# LoRaWAN_CC1310_V1_1.net
KiCad netlist of a schematic drawn in Altium Designer
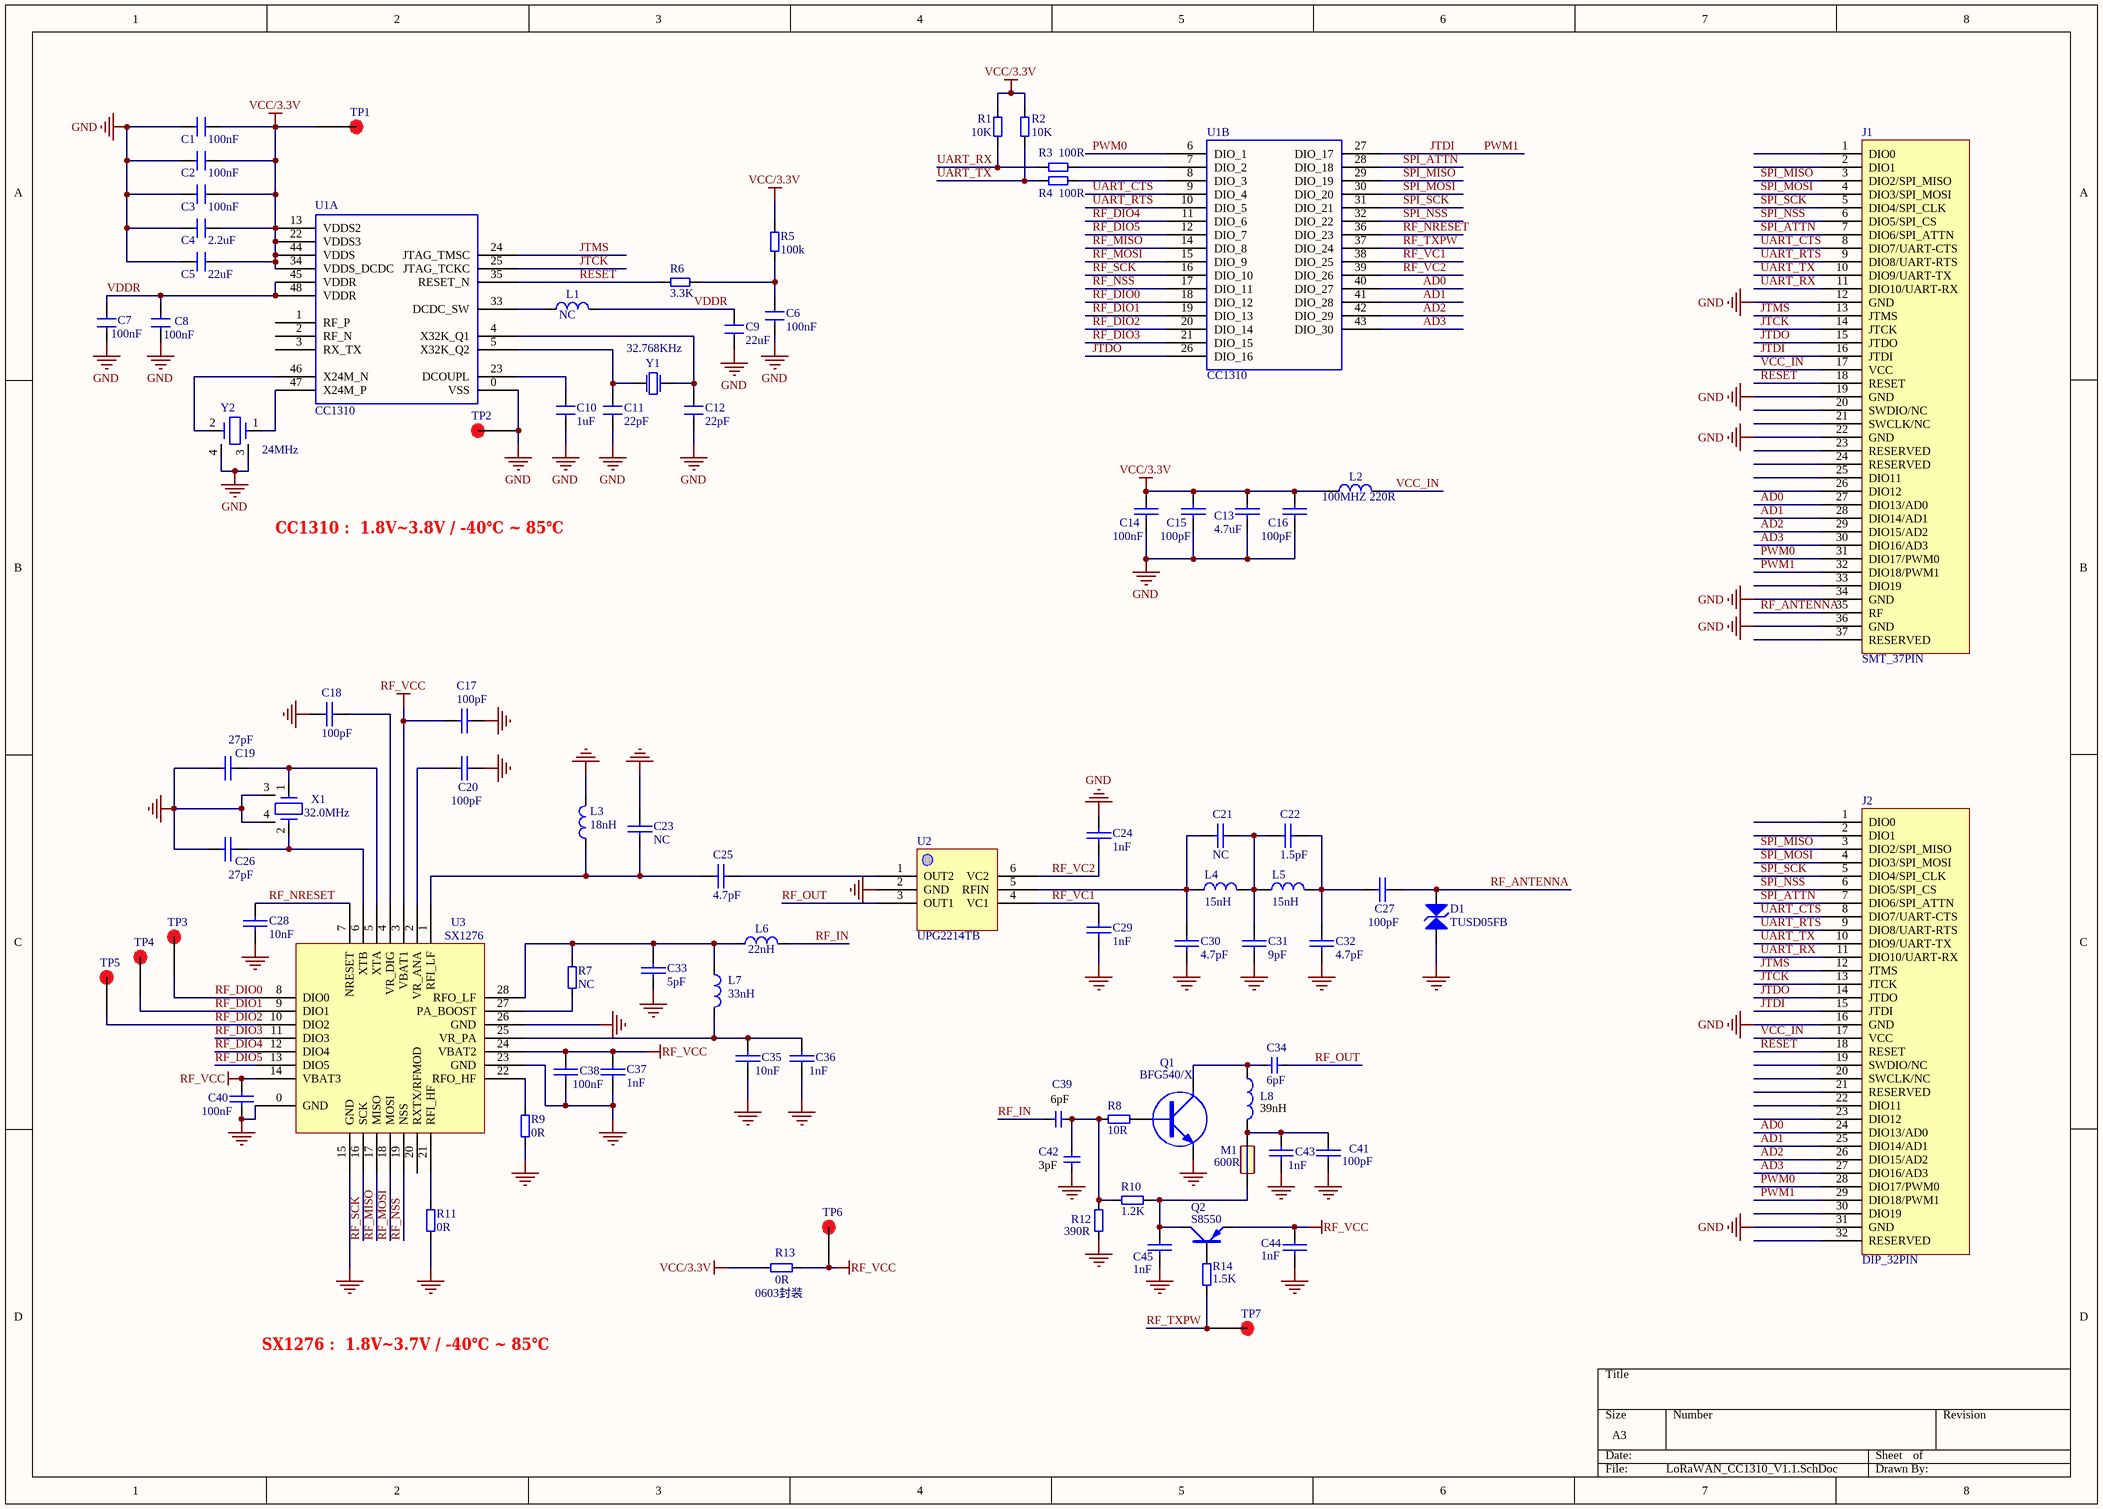
[diagram p0: LoRaWAN_CC1310_V1.1.SchDoc]

(export (version "E")
  (design (tool "Eeschema 10.0.6"))
  (components
    (comp (ref "C1") (value "100nF") (footprint "C0402") (libsource (lib "*") (part "CAP1")))
    (comp (ref "C2") (value "100nF") (footprint "C0402") (libsource (lib "*") (part "CAP1")))
    (comp (ref "C3") (value "100nF") (footprint "C0402") (libsource (lib "*") (part "CAP1")))
    (comp (ref "C4") (value "2.2uF") (footprint "C0402") (libsource (lib "*") (part "CAP1")))
    (comp (ref "C5") (value "22uF") (footprint "C0402") (libsource (lib "*") (part "CAP1")))
    (comp (ref "C6") (value "100nF") (footprint "C0402") (libsource (lib "*") (part "CAP1")))
    (comp (ref "C7") (value "100nF") (footprint "C0402") (libsource (lib "*") (part "CAP1")))
    (comp (ref "C8") (value "100nF") (footprint "C0805") (libsource (lib "*") (part "CAP1")))
    (comp (ref "C9") (value "22uF") (footprint "C0402") (libsource (lib "*") (part "CAP1")))
    (comp (ref "C10") (value "1uF") (footprint "C0402") (libsource (lib "*") (part "CAP1")))
    (comp (ref "C11") (value "22pF") (footprint "C0402") (libsource (lib "*") (part "CAP1")))
    (comp (ref "C12") (value "22pF") (footprint "C0402") (libsource (lib "*") (part "CAP1")))
    (comp (ref "C13")
      (value "4.7uF")
      (footprint "C0603")
      (description "Capacitor")
      (libsource (lib "*") (part "CAP"))
    )
    (comp (ref "C14")
      (value "100nF")
      (footprint "0402")
      (description "Capacitor")
      (libsource (lib "*") (part "CAP"))
    )
    (comp (ref "C15")
      (value "100pF")
      (footprint "0402")
      (description "Capacitor")
      (libsource (lib "*") (part "CAP"))
    )
    (comp (ref "C16")
      (value "100pF")
      (footprint "0402")
      (description "Capacitor")
      (libsource (lib "*") (part "CAP"))
    )
    (comp (ref "C17")
      (value "100pF")
      (footprint "C0402")
      (description "普通贴片电容")
      (libsource (lib "*") (part "C-SMD"))
    )
    (comp (ref "C18")
      (value "100pF")
      (footprint "C0402")
      (description "普通贴片电容")
      (libsource (lib "*") (part "C-SMD"))
    )
    (comp (ref "C19")
      (value "27pF")
      (footprint "C0402")
      (description "普通贴片电容")
      (libsource (lib "*") (part "C-SMD"))
    )
    (comp (ref "C20")
      (value "100pF")
      (footprint "C0402")
      (description "普通贴片电容")
      (libsource (lib "*") (part "C-SMD"))
    )
    (comp (ref "C21")
      (value "NC")
      (footprint "C0402")
      (description "普通贴片电容")
      (libsource (lib "*") (part "C-SMD"))
    )
    (comp (ref "C22")
      (value "1.5pF")
      (footprint "C0402")
      (description "普通贴片电容")
      (libsource (lib "*") (part "C-SMD"))
    )
    (comp (ref "C23")
      (value "NC")
      (footprint "C0402")
      (description "普通贴片电容")
      (libsource (lib "*") (part "C-SMD"))
    )
    (comp (ref "C24")
      (value "1nF")
      (footprint "C0402")
      (description "普通贴片电容")
      (libsource (lib "*") (part "C-SMD"))
    )
    (comp (ref "C25")
      (value "4.7pF")
      (footprint "C0402")
      (description "普通贴片电容")
      (libsource (lib "*") (part "C-SMD"))
    )
    (comp (ref "C26")
      (value "27pF")
      (footprint "C0402")
      (description "普通贴片电容")
      (libsource (lib "*") (part "C-SMD"))
    )
    (comp (ref "C27")
      (value "100pF")
      (footprint "C0402")
      (description "普通贴片电容")
      (libsource (lib "*") (part "C-SMD"))
    )
    (comp (ref "C28")
      (value "10nF")
      (footprint "C0402")
      (description "普通贴片电容")
      (libsource (lib "*") (part "C-SMD"))
    )
    (comp (ref "C29")
      (value "1nF")
      (footprint "C0402")
      (description "普通贴片电容")
      (libsource (lib "*") (part "C-SMD"))
    )
    (comp (ref "C30")
      (value "4.7pF")
      (footprint "C0402")
      (description "普通贴片电容")
      (libsource (lib "*") (part "C-SMD"))
    )
    (comp (ref "C31")
      (value "9pF")
      (footprint "C0402")
      (description "普通贴片电容")
      (libsource (lib "*") (part "C-SMD"))
    )
    (comp (ref "C32")
      (value "4.7pF")
      (footprint "C0402")
      (description "普通贴片电容")
      (libsource (lib "*") (part "C-SMD"))
    )
    (comp (ref "C33")
      (value "5pF")
      (footprint "C0402")
      (description "普通贴片电容")
      (libsource (lib "*") (part "C-SMD"))
    )
    (comp (ref "C34")
      (value "6pF")
      (footprint "C0402")
      (description "Capacitor")
      (libsource (lib "*") (part "CAP_S"))
    )
    (comp (ref "C35")
      (value "10nF")
      (footprint "C0402")
      (description "普通贴片电容")
      (libsource (lib "*") (part "C-SMD"))
    )
    (comp (ref "C36")
      (value "1nF")
      (footprint "C0402")
      (description "普通贴片电容")
      (libsource (lib "*") (part "C-SMD"))
    )
    (comp (ref "C37")
      (value "1nF")
      (footprint "C0402")
      (description "普通贴片电容")
      (libsource (lib "*") (part "C-SMD"))
    )
    (comp (ref "C38")
      (value "100nF")
      (footprint "C0402")
      (description "普通贴片电容")
      (libsource (lib "*") (part "C-SMD"))
    )
    (comp (ref "C39")
      (value "6pF")
      (footprint "C0402")
      (description "Capacitor")
      (libsource (lib "*") (part "CAP_S"))
    )
    (comp (ref "C40")
      (value "100nF")
      (footprint "C0402")
      (description "普通贴片电容")
      (libsource (lib "*") (part "C-SMD"))
    )
    (comp (ref "C41")
      (value "100pF")
      (footprint "C0402")
      (description "Chip C")
      (libsource (lib "*") (part "C/0603"))
    )
    (comp (ref "C42")
      (value "3pF")
      (footprint "C0402")
      (description "Capacitor")
      (libsource (lib "*") (part "CAP_S"))
    )
    (comp (ref "C43")
      (value "1nF")
      (footprint "C0402")
      (description "Chip C")
      (libsource (lib "*") (part "C/0603"))
    )
    (comp (ref "C44")
      (value "1nF")
      (footprint "C0402")
      (description "Chip C")
      (libsource (lib "*") (part "C/0603"))
    )
    (comp (ref "C45")
      (value "1nF")
      (footprint "C0402")
      (description "Chip C")
      (libsource (lib "*") (part "C/0603"))
    )
    (comp (ref "D1")
      (value "TUSD05FB")
      (footprint "ESD/SOD-323")
      (description "ESD管")
      (libsource (lib "*") (part "D-ESD"))
    )
    (comp (ref "J1") (value "SMT_37PIN") (libsource (lib "Schlib1") (part "SMT_37PIN")))
    (comp (ref "J2") (value "DIP_32PIN") (libsource (lib "Schlib1") (part "DIP_32PIN")))
    (comp (ref "L1")
      (value "NC")
      (footprint "L0402")
      (description "普通贴片电感")
      (libsource (lib "") (part "L-SMD_1"))
    )
    (comp (ref "L2")
      (value "100MHZ 220R")
      (footprint "L0402")
      (description "普通贴片电感")
      (libsource (lib "") (part "L-SMD_1"))
    )
    (comp (ref "L3")
      (value "18nH")
      (footprint "L0402")
      (description "普通贴片电感")
      (libsource (lib "*") (part "L-SMD"))
    )
    (comp (ref "L4")
      (value "15nH")
      (footprint "L0603")
      (description "普通贴片电感")
      (libsource (lib "") (part "L-SMD_1"))
    )
    (comp (ref "L5")
      (value "15nH")
      (footprint "L0603")
      (description "普通贴片电感")
      (libsource (lib "") (part "L-SMD_1"))
    )
    (comp (ref "L6")
      (value "22nH")
      (footprint "L0402")
      (description "普通贴片电感")
      (libsource (lib "") (part "L-SMD_1"))
    )
    (comp (ref "L7")
      (value "33nH")
      (footprint "L0603")
      (description "普通贴片电感")
      (libsource (lib "*") (part "L-SMD"))
    )
    (comp (ref "L8")
      (value "39nH")
      (footprint "L0603")
      (description "Chip L")
      (libsource (lib "*") (part "L/0402"))
    )
    (comp (ref "M1") (value "600R") (footprint "L0603") (libsource (lib "*") (part "MB")))
    (comp (ref "Q1") (value "BFG540/X") (footprint "BFG540/X") (libsource (lib "*") (part "NPN")))
    (comp (ref "Q2")
      (value "S8550")
      (footprint "Q/SOT-23")
      (description "Transistor")
      (libsource (lib "*") (part "PNPS"))
    )
    (comp (ref "R1") (value "10K") (footprint "R0402") (libsource (lib "*") (part "RES5")))
    (comp (ref "R2") (value "10K") (footprint "R0402") (libsource (lib "*") (part "RES5")))
    (comp (ref "R3") (value "100R") (footprint "R0402") (libsource (lib "*") (part "RES5")))
    (comp (ref "R4") (value "100R") (footprint "R0402") (libsource (lib "*") (part "RES5")))
    (comp (ref "R5") (value "100k") (footprint "R0402") (libsource (lib "*") (part "RES5")))
    (comp (ref "R6") (value "3.3K") (footprint "R0402") (libsource (lib "*") (part "RES5")))
    (comp (ref "R7")
      (value "NC")
      (footprint "R0402")
      (description "贴片电阻")
      (libsource (lib "*") (part "R-SMD"))
    )
    (comp (ref "R8")
      (value "10R")
      (footprint "R0402")
      (description "Resistance")
      (libsource (lib "*") (part "RL2"))
    )
    (comp (ref "R9")
      (value "0R")
      (footprint "R0402")
      (description "Resistance")
      (libsource (lib "*") (part "RL2"))
    )
    (comp (ref "R10")
      (value "1.2K")
      (footprint "R0402")
      (description "Resistance")
      (libsource (lib "*") (part "RL2"))
    )
    (comp (ref "R11")
      (value "0R")
      (footprint "R0402")
      (description "Resistance")
      (libsource (lib "*") (part "RL2"))
    )
    (comp (ref "R12")
      (value "390R")
      (footprint "R0402")
      (description "Resistance")
      (libsource (lib "*") (part "RL2"))
    )
    (comp (ref "R13")
      (value "0R")
      (footprint "R0603")
      (description "贴片电阻")
      (libsource (lib "*") (part "R-SMD"))
    )
    (comp (ref "R14")
      (value "1.5K")
      (footprint "R0402")
      (description "Resistance")
      (libsource (lib "*") (part "RL2"))
    )
    (comp (ref "TP1") (value "~") (footprint "TP") (libsource (lib "*") (part "Z-TP")))
    (comp (ref "TP2") (value "~") (footprint "TP") (libsource (lib "*") (part "Z-TP")))
    (comp (ref "TP3") (value "~") (footprint "TP") (libsource (lib "*") (part "Z-TP")))
    (comp (ref "TP4") (value "~") (footprint "TP") (libsource (lib "*") (part "Z-TP")))
    (comp (ref "TP5") (value "~") (footprint "TP") (libsource (lib "*") (part "Z-TP")))
    (comp (ref "TP6") (value "~") (footprint "TP") (libsource (lib "*") (part "Z-TP")))
    (comp (ref "TP7") (value "~") (footprint "TP") (libsource (lib "*") (part "Z-TP")))
    (comp (ref "U1") (value "CC1310") (footprint "QFN-48/0.5") (libsource (lib "*") (part "U-RF-CC1310")))
    (comp (ref "U2") (value "UPG2214TB") (footprint "SOT-363") (libsource (lib "*") (part "U-Z-UPG2214TB")))
    (comp (ref "U3") (value "SX1276") (footprint "QFN-28/0.65") (libsource (lib "*") (part "U-RF-SX1276")))
    (comp (ref "X1") (value "32.0MHz") (footprint "XTAL-3225") (libsource (lib "*") (part "Z-XTAL-4P")))
    (comp (ref "Y1") (value "32.768KHz") (footprint "XTAL-3215") (libsource (lib "*") (part "CRYSTAL")))
    (comp (ref "Y2") (value "24MHz") (footprint "XTAL-3225") (libsource (lib "") (part "Z-XTAL-4P_1")))
  )
  (nets
    (net (code "1") (name "/AD0") (class "Default")
      (node (ref "J1") (pin "27") (pinfunction "DIO13/AD0_27") (pintype "passive"))
      (node (ref "J2") (pin "24") (pinfunction "DIO13/AD0_24") (pintype "passive"))
      (node (ref "U1") (pin "40") (pinfunction "DIO_27_40") (pintype "passive"))
    )
    (net (code "2") (name "/AD1") (class "Default")
      (node (ref "J1") (pin "28") (pinfunction "DIO14/AD1_28") (pintype "passive"))
      (node (ref "J2") (pin "25") (pinfunction "DIO14/AD1_25") (pintype "passive"))
      (node (ref "U1") (pin "41") (pinfunction "DIO_28_41") (pintype "passive"))
    )
    (net (code "3") (name "/AD2") (class "Default")
      (node (ref "J1") (pin "29") (pinfunction "DIO15/AD2_29") (pintype "passive"))
      (node (ref "J2") (pin "26") (pinfunction "DIO15/AD2_26") (pintype "passive"))
      (node (ref "U1") (pin "42") (pinfunction "DIO_29_42") (pintype "passive"))
    )
    (net (code "4") (name "/AD3") (class "Default")
      (node (ref "J1") (pin "30") (pinfunction "DIO16/AD3_30") (pintype "passive"))
      (node (ref "J2") (pin "27") (pinfunction "DIO16/AD3_27") (pintype "passive"))
      (node (ref "U1") (pin "43") (pinfunction "DIO_30_43") (pintype "passive"))
    )
    (net (code "5") (name "/JTCK") (class "Default")
      (node (ref "J1") (pin "14") (pinfunction "JTCK_14") (pintype "passive"))
      (node (ref "J2") (pin "13") (pinfunction "JTCK_13") (pintype "passive"))
      (node (ref "U1") (pin "25") (pinfunction "JTAG_TCKC_25") (pintype "passive"))
    )
    (net (code "6") (name "/JTDI") (class "Default")
      (node (ref "J1") (pin "16") (pinfunction "JTDI_16") (pintype "passive"))
      (node (ref "J1") (pin "32") (pinfunction "DIO18/PWM1_32") (pintype "passive"))
      (node (ref "J2") (pin "15") (pinfunction "JTDI_15") (pintype "passive"))
      (node (ref "J2") (pin "29") (pinfunction "DIO18/PWM1_29") (pintype "passive"))
      (node (ref "U1") (pin "27") (pinfunction "DIO_17_27") (pintype "passive"))
    )
    (net (code "7") (name "/JTDO") (class "Default")
      (node (ref "J1") (pin "15") (pinfunction "JTDO_15") (pintype "passive"))
      (node (ref "J2") (pin "14") (pinfunction "JTDO_14") (pintype "passive"))
      (node (ref "U1") (pin "26") (pinfunction "DIO_16_26") (pintype "passive"))
    )
    (net (code "8") (name "/JTMS") (class "Default")
      (node (ref "J1") (pin "13") (pinfunction "JTMS_13") (pintype "passive"))
      (node (ref "J2") (pin "12") (pinfunction "JTMS_12") (pintype "passive"))
      (node (ref "U1") (pin "24") (pinfunction "JTAG_TMSC_24") (pintype "passive"))
    )
    (net (code "9") (name "/PWM0") (class "Default")
      (node (ref "J1") (pin "31") (pinfunction "DIO17/PWM0_31") (pintype "passive"))
      (node (ref "J2") (pin "28") (pinfunction "DIO17/PWM0_28") (pintype "passive"))
      (node (ref "U1") (pin "6") (pinfunction "DIO_1_6") (pintype "passive"))
    )
    (net (code "10") (name "/RESET") (class "Default")
      (node (ref "J1") (pin "18") (pinfunction "RESET_18") (pintype "passive"))
      (node (ref "J2") (pin "18") (pinfunction "RESET_18") (pintype "passive"))
      (node (ref "R6") (pin "1") (pinfunction "1_1") (pintype "passive"))
      (node (ref "U1") (pin "35") (pinfunction "RESET_N_35") (pintype "passive"))
    )
    (net (code "11") (name "/RF_ANTENNA") (class "Default")
      (node (ref "C27") (pin "2") (pintype "passive"))
      (node (ref "D1") (pin "2") (pintype "passive"))
      (node (ref "J1") (pin "35") (pinfunction "RF_35") (pintype "passive"))
    )
    (net (code "12") (name "/RF_DIO0") (class "Default")
      (node (ref "TP3") (pin "1") (pinfunction "1_1") (pintype "passive"))
      (node (ref "U1") (pin "18") (pinfunction "DIO_12_18") (pintype "passive"))
      (node (ref "U3") (pin "8") (pinfunction "DIO0_8") (pintype "passive"))
    )
    (net (code "13") (name "/RF_DIO1") (class "Default")
      (node (ref "TP4") (pin "1") (pinfunction "1_1") (pintype "passive"))
      (node (ref "U1") (pin "19") (pinfunction "DIO_13_19") (pintype "passive"))
      (node (ref "U3") (pin "9") (pinfunction "DIO1_9") (pintype "passive"))
    )
    (net (code "14") (name "/RF_DIO2") (class "Default")
      (node (ref "TP5") (pin "1") (pinfunction "1_1") (pintype "passive"))
      (node (ref "U1") (pin "20") (pinfunction "DIO_14_20") (pintype "passive"))
      (node (ref "U3") (pin "10") (pinfunction "DIO2_10") (pintype "passive"))
    )
    (net (code "15") (name "/RF_DIO3") (class "Default")
      (node (ref "U1") (pin "21") (pinfunction "DIO_15_21") (pintype "passive"))
      (node (ref "U3") (pin "11") (pinfunction "DIO3_11") (pintype "passive"))
    )
    (net (code "16") (name "/RF_DIO4") (class "Default")
      (node (ref "U1") (pin "11") (pinfunction "DIO_6_11") (pintype "passive"))
      (node (ref "U3") (pin "12") (pinfunction "DIO4_12") (pintype "passive"))
    )
    (net (code "17") (name "/RF_DIO5") (class "Default")
      (node (ref "U1") (pin "12") (pinfunction "DIO_7_12") (pintype "passive"))
      (node (ref "U3") (pin "13") (pinfunction "DIO5_13") (pintype "passive"))
    )
    (net (code "18") (name "/RF_IN") (class "Default")
      (node (ref "C39") (pin "2") (pinfunction "2_2") (pintype "passive"))
      (node (ref "L6") (pin "2") (pintype "passive"))
    )
    (net (code "19") (name "/RF_MISO") (class "Default")
      (node (ref "U1") (pin "14") (pinfunction "DIO_8_14") (pintype "passive"))
      (node (ref "U3") (pin "17") (pinfunction "MISO_17") (pintype "passive"))
    )
    (net (code "20") (name "/RF_MOSI") (class "Default")
      (node (ref "U1") (pin "15") (pinfunction "DIO_9_15") (pintype "passive"))
      (node (ref "U3") (pin "18") (pinfunction "MOSI_18") (pintype "passive"))
    )
    (net (code "21") (name "/RF_NRESET") (class "Default")
      (node (ref "C28") (pin "1") (pinfunction "1_1") (pintype "passive"))
      (node (ref "U1") (pin "36") (pinfunction "DIO_23_36") (pintype "passive"))
      (node (ref "U3") (pin "7") (pinfunction "NRESET_7") (pintype "passive"))
    )
    (net (code "22") (name "/RF_NSS") (class "Default")
      (node (ref "U1") (pin "17") (pinfunction "DIO_11_17") (pintype "passive"))
      (node (ref "U3") (pin "19") (pinfunction "NSS_19") (pintype "passive"))
    )
    (net (code "23") (name "/RF_OUT") (class "Default")
      (node (ref "C34") (pin "1") (pinfunction "1_1") (pintype "passive"))
      (node (ref "U2") (pin "3") (pinfunction "OUT1_3") (pintype "passive"))
    )
    (net (code "24") (name "/RF_SCK") (class "Default")
      (node (ref "U1") (pin "16") (pinfunction "DIO_10_16") (pintype "passive"))
      (node (ref "U3") (pin "16") (pinfunction "SCK_16") (pintype "passive"))
    )
    (net (code "25") (name "/RF_TXPW") (class "Default")
      (node (ref "R14") (pin "1") (pintype "passive"))
      (node (ref "TP7") (pin "1") (pinfunction "1_1") (pintype "passive"))
      (node (ref "U1") (pin "37") (pinfunction "DIO_24_37") (pintype "passive"))
    )
    (net (code "26") (name "/RF_VC1") (class "Default")
      (node (ref "C29") (pin "1") (pinfunction "1_1") (pintype "passive"))
      (node (ref "U1") (pin "38") (pinfunction "DIO_25_38") (pintype "passive"))
      (node (ref "U2") (pin "4") (pinfunction "VC1_4") (pintype "passive"))
    )
    (net (code "27") (name "/RF_VC2") (class "Default")
      (node (ref "C24") (pin "1") (pinfunction "1_1") (pintype "passive"))
      (node (ref "U1") (pin "39") (pinfunction "DIO_26_39") (pintype "passive"))
      (node (ref "U2") (pin "6") (pinfunction "VC2_6") (pintype "passive"))
    )
    (net (code "28") (name "/SPI_ATTN") (class "Default")
      (node (ref "J1") (pin "7") (pinfunction "DIO6/SPI_ATTN_7") (pintype "passive"))
      (node (ref "J2") (pin "7") (pinfunction "DIO6/SPI_ATTN_7") (pintype "passive"))
      (node (ref "U1") (pin "28") (pinfunction "DIO_18_28") (pintype "passive"))
    )
    (net (code "29") (name "/SPI_MISO") (class "Default")
      (node (ref "J1") (pin "3") (pinfunction "DIO2/SPI_MISO_3") (pintype "passive"))
      (node (ref "J2") (pin "3") (pinfunction "DIO2/SPI_MISO_3") (pintype "passive"))
      (node (ref "U1") (pin "29") (pinfunction "DIO_19_29") (pintype "passive"))
    )
    (net (code "30") (name "/SPI_MOSI") (class "Default")
      (node (ref "J1") (pin "4") (pinfunction "DIO3/SPI_MOSI_4") (pintype "passive"))
      (node (ref "J2") (pin "4") (pinfunction "DIO3/SPI_MOSI_4") (pintype "passive"))
      (node (ref "U1") (pin "30") (pinfunction "DIO_20_30") (pintype "passive"))
    )
    (net (code "31") (name "/SPI_NSS") (class "Default")
      (node (ref "J1") (pin "6") (pinfunction "DIO5/SPI_CS_6") (pintype "passive"))
      (node (ref "J2") (pin "6") (pinfunction "DIO5/SPI_CS_6") (pintype "passive"))
      (node (ref "U1") (pin "32") (pinfunction "DIO_22_32") (pintype "passive"))
    )
    (net (code "32") (name "/SPI_SCK") (class "Default")
      (node (ref "J1") (pin "5") (pinfunction "DIO4/SPI_CLK_5") (pintype "passive"))
      (node (ref "J2") (pin "5") (pinfunction "DIO4/SPI_CLK_5") (pintype "passive"))
      (node (ref "U1") (pin "31") (pinfunction "DIO_21_31") (pintype "passive"))
    )
    (net (code "33") (name "/UART_CTS") (class "Default")
      (node (ref "J1") (pin "8") (pinfunction "DIO7/UART-CTS_8") (pintype "passive"))
      (node (ref "J2") (pin "8") (pinfunction "DIO7/UART-CTS_8") (pintype "passive"))
      (node (ref "U1") (pin "9") (pinfunction "DIO_4_9") (pintype "passive"))
    )
    (net (code "34") (name "/UART_RTS") (class "Default")
      (node (ref "J1") (pin "9") (pinfunction "DIO8/UART-RTS_9") (pintype "passive"))
      (node (ref "J2") (pin "9") (pinfunction "DIO8/UART-RTS_9") (pintype "passive"))
      (node (ref "U1") (pin "10") (pinfunction "DIO_5_10") (pintype "passive"))
    )
    (net (code "35") (name "/UART_RX") (class "Default")
      (node (ref "J1") (pin "11") (pinfunction "DIO10/UART-RX_11") (pintype "passive"))
      (node (ref "J2") (pin "11") (pinfunction "DIO10/UART-RX_11") (pintype "passive"))
      (node (ref "R1") (pin "1") (pinfunction "1_1") (pintype "passive"))
      (node (ref "R3") (pin "1") (pinfunction "1_1") (pintype "passive"))
    )
    (net (code "36") (name "/UART_TX") (class "Default")
      (node (ref "J1") (pin "10") (pinfunction "DIO9/UART-TX_10") (pintype "passive"))
      (node (ref "J2") (pin "10") (pinfunction "DIO9/UART-TX_10") (pintype "passive"))
      (node (ref "R2") (pin "1") (pinfunction "1_1") (pintype "passive"))
      (node (ref "R4") (pin "1") (pinfunction "1_1") (pintype "passive"))
    )
    (net (code "37") (name "/VCC_IN") (class "Default")
      (node (ref "J1") (pin "17") (pinfunction "VCC_17") (pintype "passive"))
      (node (ref "J2") (pin "17") (pinfunction "VCC_17") (pintype "passive"))
      (node (ref "L2") (pin "2") (pintype "passive"))
    )
    (net (code "38") (name "/VDDR") (class "Default")
      (node (ref "C7") (pin "2") (pintype "passive"))
      (node (ref "C8") (pin "2") (pintype "passive"))
      (node (ref "C9") (pin "1") (pinfunction "1_1") (pintype "passive"))
      (node (ref "L1") (pin "2") (pintype "passive"))
      (node (ref "U1") (pin "45") (pinfunction "VDDR_45") (pintype "passive"))
      (node (ref "U1") (pin "48") (pinfunction "VDDR_48") (pintype "passive"))
    )
    (net (code "39") (name "GND") (class "Default")
      (node (ref "C1") (pin "1") (pinfunction "1_1") (pintype "passive"))
      (node (ref "C10") (pin "1") (pinfunction "1_1") (pintype "passive"))
      (node (ref "C11") (pin "1") (pinfunction "1_1") (pintype "passive"))
      (node (ref "C12") (pin "2") (pintype "passive"))
      (node (ref "C13") (pin "2") (pinfunction "2_2") (pintype "passive"))
      (node (ref "C14") (pin "2") (pinfunction "2_2") (pintype "passive"))
      (node (ref "C15") (pin "2") (pinfunction "2_2") (pintype "passive"))
      (node (ref "C16") (pin "2") (pinfunction "2_2") (pintype "passive"))
      (node (ref "C17") (pin "2") (pintype "passive"))
      (node (ref "C18") (pin "2") (pintype "passive"))
      (node (ref "C19") (pin "1") (pinfunction "1_1") (pintype "passive"))
      (node (ref "C2") (pin "1") (pinfunction "1_1") (pintype "passive"))
      (node (ref "C20") (pin "2") (pintype "passive"))
      (node (ref "C23") (pin "1") (pinfunction "1_1") (pintype "passive"))
      (node (ref "C24") (pin "2") (pintype "passive"))
      (node (ref "C26") (pin "1") (pinfunction "1_1") (pintype "passive"))
      (node (ref "C28") (pin "2") (pintype "passive"))
      (node (ref "C29") (pin "2") (pintype "passive"))
      (node (ref "C3") (pin "1") (pinfunction "1_1") (pintype "passive"))
      (node (ref "C30") (pin "2") (pintype "passive"))
      (node (ref "C31") (pin "2") (pintype "passive"))
      (node (ref "C32") (pin "2") (pintype "passive"))
      (node (ref "C33") (pin "2") (pintype "passive"))
      (node (ref "C35") (pin "2") (pintype "passive"))
      (node (ref "C36") (pin "2") (pintype "passive"))
      (node (ref "C37") (pin "2") (pintype "passive"))
      (node (ref "C38") (pin "2") (pintype "passive"))
      (node (ref "C4") (pin "1") (pinfunction "1_1") (pintype "passive"))
      (node (ref "C40") (pin "2") (pintype "passive"))
      (node (ref "C41") (pin "2") (pinfunction "2_2") (pintype "passive"))
      (node (ref "C42") (pin "1") (pinfunction "1_1") (pintype "passive"))
      (node (ref "C43") (pin "2") (pinfunction "2_2") (pintype "passive"))
      (node (ref "C44") (pin "2") (pinfunction "2_2") (pintype "passive"))
      (node (ref "C45") (pin "2") (pinfunction "2_2") (pintype "passive"))
      (node (ref "C5") (pin "1") (pinfunction "1_1") (pintype "passive"))
      (node (ref "C6") (pin "1") (pinfunction "1_1") (pintype "passive"))
      (node (ref "C7") (pin "1") (pinfunction "1_1") (pintype "passive"))
      (node (ref "C8") (pin "1") (pinfunction "1_1") (pintype "passive"))
      (node (ref "C9") (pin "2") (pintype "passive"))
      (node (ref "D1") (pin "1") (pintype "passive"))
      (node (ref "J1") (pin "12") (pinfunction "GND_12") (pintype "passive"))
      (node (ref "J1") (pin "19") (pinfunction "GND_19") (pintype "passive"))
      (node (ref "J1") (pin "22") (pinfunction "GND_22") (pintype "passive"))
      (node (ref "J1") (pin "34") (pinfunction "GND_34") (pintype "passive"))
      (node (ref "J1") (pin "36") (pinfunction "GND_36") (pintype "passive"))
      (node (ref "J2") (pin "16") (pinfunction "GND_16") (pintype "passive"))
      (node (ref "J2") (pin "31") (pinfunction "GND_31") (pintype "passive"))
      (node (ref "L3") (pin "2") (pintype "passive"))
      (node (ref "Q1") (pin "E") (pinfunction "E_E") (pintype "passive"))
      (node (ref "R11") (pin "2") (pintype "passive"))
      (node (ref "R12") (pin "1") (pintype "passive"))
      (node (ref "R9") (pin "2") (pintype "passive"))
      (node (ref "TP2") (pin "1") (pinfunction "1_1") (pintype "passive"))
      (node (ref "U1") (pin "0") (pinfunction "VSS_0") (pintype "passive"))
      (node (ref "U2") (pin "2") (pinfunction "GND_2") (pintype "passive"))
      (node (ref "U3") (pin "0") (pinfunction "GND_0") (pintype "passive"))
      (node (ref "U3") (pin "15") (pinfunction "GND_15") (pintype "passive"))
      (node (ref "U3") (pin "23") (pinfunction "GND_23") (pintype "passive"))
      (node (ref "U3") (pin "26") (pinfunction "GND_26") (pintype "passive"))
      (node (ref "X1") (pin "3") (pinfunction "3_3") (pintype "passive"))
      (node (ref "X1") (pin "4") (pinfunction "4_4") (pintype "passive"))
      (node (ref "Y2") (pin "3") (pinfunction "3_3") (pintype "passive"))
      (node (ref "Y2") (pin "4") (pinfunction "4_4") (pintype "passive"))
    )
    (net (code "40") (name "Net-(C6-Pad2)") (class "Default")
      (node (ref "C6") (pin "2") (pintype "passive"))
      (node (ref "R5") (pin "2") (pinfunction "2_2") (pintype "passive"))
      (node (ref "R6") (pin "2") (pinfunction "2_2") (pintype "passive"))
    )
    (net (code "41") (name "Net-(C21-Pad2)") (class "Default")
      (node (ref "C21") (pin "2") (pintype "passive"))
      (node (ref "C22") (pin "1") (pinfunction "1_1") (pintype "passive"))
      (node (ref "C31") (pin "1") (pinfunction "1_1") (pintype "passive"))
      (node (ref "L4") (pin "2") (pintype "passive"))
      (node (ref "L5") (pin "1") (pintype "passive"))
    )
    (net (code "42") (name "Net-(C22-Pad2)") (class "Default")
      (node (ref "C22") (pin "2") (pintype "passive"))
      (node (ref "C27") (pin "1") (pinfunction "1_1") (pintype "passive"))
      (node (ref "C32") (pin "1") (pinfunction "1_1") (pintype "passive"))
      (node (ref "L5") (pin "2") (pintype "passive"))
    )
    (net (code "43") (name "Net-(C34-Pad2)") (class "Default")
      (node (ref "C34") (pin "2") (pinfunction "2_2") (pintype "passive"))
      (node (ref "L8") (pin "2") (pinfunction "2_2") (pintype "passive"))
      (node (ref "Q1") (pin "C") (pinfunction "C_C") (pintype "passive"))
    )
    (net (code "44") (name "Net-(C39-Pad1)") (class "Default")
      (node (ref "C39") (pin "1") (pinfunction "1_1") (pintype "passive"))
      (node (ref "C42") (pin "2") (pinfunction "2_2") (pintype "passive"))
      (node (ref "R10") (pin "1") (pintype "passive"))
      (node (ref "R12") (pin "2") (pintype "passive"))
      (node (ref "R8") (pin "1") (pintype "passive"))
    )
    (net (code "45") (name "Net-(C41-Pad1)") (class "Default")
      (node (ref "C41") (pin "1") (pinfunction "1_1") (pintype "passive"))
      (node (ref "C43") (pin "1") (pinfunction "1_1") (pintype "passive"))
      (node (ref "L8") (pin "1") (pinfunction "1_1") (pintype "passive"))
      (node (ref "M1") (pin "1") (pinfunction "1_1") (pintype "passive"))
    )
    (net (code "46") (name "Net-(C45-Pad1)") (class "Default")
      (node (ref "C45") (pin "1") (pinfunction "1_1") (pintype "passive"))
      (node (ref "M1") (pin "2") (pinfunction "2_2") (pintype "passive"))
      (node (ref "Q2") (pin "C") (pintype "passive"))
      (node (ref "R10") (pin "2") (pintype "passive"))
    )
    (net (code "47") (name "Net-(Q1-PadB)") (class "Default")
      (node (ref "Q1") (pin "B") (pinfunction "B_B") (pintype "passive"))
      (node (ref "R8") (pin "2") (pintype "passive"))
    )
    (net (code "48") (name "Net-(Q2-PadB)") (class "Default")
      (node (ref "Q2") (pin "B") (pintype "passive"))
      (node (ref "R14") (pin "2") (pintype "passive"))
    )
    (net (code "49") (name "Net-(U1A-DCDC_SW)") (class "Default")
      (node (ref "L1") (pin "1") (pintype "passive"))
      (node (ref "U1") (pin "33") (pinfunction "DCDC_SW_33") (pintype "passive"))
    )
    (net (code "50") (name "Net-(U1A-DCOUPL)") (class "Default")
      (node (ref "C10") (pin "2") (pintype "passive"))
      (node (ref "U1") (pin "23") (pinfunction "DCOUPL_23") (pintype "passive"))
    )
    (net (code "51") (name "Net-(U1A-X24M_N)") (class "Default")
      (node (ref "U1") (pin "46") (pinfunction "X24M_N_46") (pintype "passive"))
      (node (ref "Y2") (pin "2") (pinfunction "2_2") (pintype "passive"))
    )
    (net (code "52") (name "Net-(U1A-X24M_P)") (class "Default")
      (node (ref "U1") (pin "47") (pinfunction "X24M_P_47") (pintype "passive"))
      (node (ref "Y2") (pin "1") (pinfunction "1_1") (pintype "passive"))
    )
    (net (code "53") (name "Net-(U1A-X32K_Q1)") (class "Default")
      (node (ref "C12") (pin "1") (pinfunction "1_1") (pintype "passive"))
      (node (ref "U1") (pin "4") (pinfunction "X32K_Q1_4") (pintype "passive"))
      (node (ref "Y1") (pin "2") (pinfunction "P2_2") (pintype "passive"))
    )
    (net (code "54") (name "Net-(U1A-X32K_Q2)") (class "Default")
      (node (ref "C11") (pin "2") (pintype "passive"))
      (node (ref "U1") (pin "5") (pinfunction "X32K_Q2_5") (pintype "passive"))
      (node (ref "Y1") (pin "1") (pinfunction "P1_1") (pintype "passive"))
    )
    (net (code "55") (name "Net-(U1B-DIO_2)") (class "Default")
      (node (ref "R3") (pin "2") (pinfunction "2_2") (pintype "passive"))
      (node (ref "U1") (pin "7") (pinfunction "DIO_2_7") (pintype "passive"))
    )
    (net (code "56") (name "Net-(U1B-DIO_3)") (class "Default")
      (node (ref "R4") (pin "2") (pinfunction "2_2") (pintype "passive"))
      (node (ref "U1") (pin "8") (pinfunction "DIO_3_8") (pintype "passive"))
    )
    (net (code "57") (name "Net-(U2-OUT2)") (class "Default")
      (node (ref "C25") (pin "2") (pintype "passive"))
      (node (ref "U2") (pin "1") (pinfunction "OUT2_1") (pintype "passive"))
    )
    (net (code "58") (name "Net-(U2-RFIN)") (class "Default")
      (node (ref "C21") (pin "1") (pinfunction "1_1") (pintype "passive"))
      (node (ref "C30") (pin "1") (pinfunction "1_1") (pintype "passive"))
      (node (ref "L4") (pin "1") (pintype "passive"))
      (node (ref "U2") (pin "5") (pinfunction "RFIN_5") (pintype "passive"))
    )
    (net (code "59") (name "Net-(U3-PA_BOOST)") (class "Default")
      (node (ref "R7") (pin "1") (pinfunction "1_1") (pintype "passive"))
      (node (ref "U3") (pin "27") (pinfunction "PA_BOOST_27") (pintype "passive"))
    )
    (net (code "60") (name "Net-(U3-RFI_HF)") (class "Default")
      (node (ref "R11") (pin "1") (pintype "passive"))
      (node (ref "U3") (pin "21") (pinfunction "RFI_HF_21") (pintype "passive"))
    )
    (net (code "61") (name "Net-(U3-RFI_LF)") (class "Default")
      (node (ref "C23") (pin "2") (pintype "passive"))
      (node (ref "C25") (pin "1") (pinfunction "1_1") (pintype "passive"))
      (node (ref "L3") (pin "1") (pintype "passive"))
      (node (ref "U3") (pin "1") (pinfunction "RFI_LF_1") (pintype "passive"))
    )
    (net (code "62") (name "Net-(U3-RFO_HF)") (class "Default")
      (node (ref "R9") (pin "1") (pintype "passive"))
      (node (ref "U3") (pin "22") (pinfunction "RFO_HF_22") (pintype "passive"))
    )
    (net (code "63") (name "Net-(U3-RFO_LF)") (class "Default")
      (node (ref "C33") (pin "1") (pinfunction "1_1") (pintype "passive"))
      (node (ref "L6") (pin "1") (pintype "passive"))
      (node (ref "L7") (pin "1") (pintype "passive"))
      (node (ref "R7") (pin "2") (pinfunction "2_2") (pintype "passive"))
      (node (ref "U3") (pin "28") (pinfunction "RFO_LF_28") (pintype "passive"))
    )
    (net (code "64") (name "Net-(U3-VR_ANA)") (class "Default")
      (node (ref "C20") (pin "1") (pinfunction "1_1") (pintype "passive"))
      (node (ref "U3") (pin "2") (pinfunction "VR_ANA_2") (pintype "passive"))
    )
    (net (code "65") (name "Net-(U3-VR_DIG)") (class "Default")
      (node (ref "C18") (pin "1") (pinfunction "1_1") (pintype "passive"))
      (node (ref "U3") (pin "4") (pinfunction "VR_DIG_4") (pintype "passive"))
    )
    (net (code "66") (name "Net-(U3-VR_PA)") (class "Default")
      (node (ref "C35") (pin "1") (pinfunction "1_1") (pintype "passive"))
      (node (ref "C36") (pin "1") (pinfunction "1_1") (pintype "passive"))
      (node (ref "L7") (pin "2") (pintype "passive"))
      (node (ref "U3") (pin "25") (pinfunction "VR_PA_25") (pintype "passive"))
    )
    (net (code "67") (name "Net-(U3-XTA)") (class "Default")
      (node (ref "C19") (pin "2") (pintype "passive"))
      (node (ref "U3") (pin "5") (pinfunction "XTA_5") (pintype "passive"))
      (node (ref "X1") (pin "1") (pinfunction "1_1") (pintype "passive"))
    )
    (net (code "68") (name "Net-(U3-XTB)") (class "Default")
      (node (ref "C26") (pin "2") (pintype "passive"))
      (node (ref "U3") (pin "6") (pinfunction "XTB_6") (pintype "passive"))
      (node (ref "X1") (pin "2") (pinfunction "2_2") (pintype "passive"))
    )
    (net (code "69") (name "RF_VCC") (class "Default")
      (node (ref "C17") (pin "1") (pinfunction "1_1") (pintype "passive"))
      (node (ref "C37") (pin "1") (pinfunction "1_1") (pintype "passive"))
      (node (ref "C38") (pin "1") (pinfunction "1_1") (pintype "passive"))
      (node (ref "C40") (pin "1") (pinfunction "1_1") (pintype "passive"))
      (node (ref "C44") (pin "1") (pinfunction "1_1") (pintype "passive"))
      (node (ref "Q2") (pin "E") (pintype "passive"))
      (node (ref "R13") (pin "2") (pinfunction "2_2") (pintype "passive"))
      (node (ref "TP6") (pin "1") (pinfunction "1_1") (pintype "passive"))
      (node (ref "U3") (pin "14") (pinfunction "VBAT3_14") (pintype "passive"))
      (node (ref "U3") (pin "24") (pinfunction "VBAT2_24") (pintype "passive"))
      (node (ref "U3") (pin "3") (pinfunction "VBAT1_3") (pintype "passive"))
    )
    (net (code "70") (name "VCC{slash}3.3V") (class "Default")
      (node (ref "C1") (pin "2") (pintype "passive"))
      (node (ref "C13") (pin "1") (pinfunction "1_1") (pintype "passive"))
      (node (ref "C14") (pin "1") (pinfunction "1_1") (pintype "passive"))
      (node (ref "C15") (pin "1") (pinfunction "1_1") (pintype "passive"))
      (node (ref "C16") (pin "1") (pinfunction "1_1") (pintype "passive"))
      (node (ref "C2") (pin "2") (pintype "passive"))
      (node (ref "C3") (pin "2") (pintype "passive"))
      (node (ref "C4") (pin "2") (pintype "passive"))
      (node (ref "C5") (pin "2") (pintype "passive"))
      (node (ref "L2") (pin "1") (pintype "passive"))
      (node (ref "R1") (pin "2") (pinfunction "2_2") (pintype "passive"))
      (node (ref "R13") (pin "1") (pinfunction "1_1") (pintype "passive"))
      (node (ref "R2") (pin "2") (pinfunction "2_2") (pintype "passive"))
      (node (ref "R5") (pin "1") (pinfunction "1_1") (pintype "passive"))
      (node (ref "TP1") (pin "1") (pinfunction "1_1") (pintype "passive"))
      (node (ref "U1") (pin "13") (pinfunction "VDDS2_13") (pintype "passive"))
      (node (ref "U1") (pin "22") (pinfunction "VDDS3_22") (pintype "passive"))
      (node (ref "U1") (pin "34") (pinfunction "VDDS_DCDC_34") (pintype "passive"))
      (node (ref "U1") (pin "44") (pinfunction "VDDS_44") (pintype "passive"))
    )
    (net (code "71") (name "unconnected-(J1-DIO0-Pad1)") (class "Default")
      (node (ref "J1") (pin "1") (pinfunction "DIO0_1") (pintype "passive"))
    )
    (net (code "72") (name "unconnected-(J1-DIO1-Pad2)") (class "Default")
      (node (ref "J1") (pin "2") (pinfunction "DIO1_2") (pintype "passive"))
    )
    (net (code "73") (name "unconnected-(J1-DIO11-Pad25)") (class "Default")
      (node (ref "J1") (pin "25") (pinfunction "DIO11_25") (pintype "passive"))
    )
    (net (code "74") (name "unconnected-(J1-DIO12-Pad26)") (class "Default")
      (node (ref "J1") (pin "26") (pinfunction "DIO12_26") (pintype "passive"))
    )
    (net (code "75") (name "unconnected-(J1-DIO19-Pad33)") (class "Default")
      (node (ref "J1") (pin "33") (pinfunction "DIO19_33") (pintype "passive"))
    )
    (net (code "76") (name "unconnected-(J1-RESERVED-Pad23)") (class "Default")
      (node (ref "J1") (pin "23") (pinfunction "RESERVED_23") (pintype "passive"))
    )
    (net (code "77") (name "unconnected-(J1-RESERVED-Pad24)") (class "Default")
      (node (ref "J1") (pin "24") (pinfunction "RESERVED_24") (pintype "passive"))
    )
    (net (code "78") (name "unconnected-(J1-RESERVED-Pad37)") (class "Default")
      (node (ref "J1") (pin "37") (pinfunction "RESERVED_37") (pintype "passive"))
    )
    (net (code "79") (name "unconnected-(J1-SWCLK{slash}NC-Pad21)") (class "Default")
      (node (ref "J1") (pin "21") (pinfunction "SWCLK/NC_21") (pintype "passive"))
    )
    (net (code "80") (name "unconnected-(J1-SWDIO{slash}NC-Pad20)") (class "Default")
      (node (ref "J1") (pin "20") (pinfunction "SWDIO/NC_20") (pintype "passive"))
    )
    (net (code "81") (name "unconnected-(J2-DIO0-Pad1)") (class "Default")
      (node (ref "J2") (pin "1") (pinfunction "DIO0_1") (pintype "passive"))
    )
    (net (code "82") (name "unconnected-(J2-DIO1-Pad2)") (class "Default")
      (node (ref "J2") (pin "2") (pinfunction "DIO1_2") (pintype "passive"))
    )
    (net (code "83") (name "unconnected-(J2-DIO11-Pad22)") (class "Default")
      (node (ref "J2") (pin "22") (pinfunction "DIO11_22") (pintype "passive"))
    )
    (net (code "84") (name "unconnected-(J2-DIO12-Pad23)") (class "Default")
      (node (ref "J2") (pin "23") (pinfunction "DIO12_23") (pintype "passive"))
    )
    (net (code "85") (name "unconnected-(J2-DIO19-Pad30)") (class "Default")
      (node (ref "J2") (pin "30") (pinfunction "DIO19_30") (pintype "passive"))
    )
    (net (code "86") (name "unconnected-(J2-RESERVED-Pad21)") (class "Default")
      (node (ref "J2") (pin "21") (pinfunction "RESERVED_21") (pintype "passive"))
    )
    (net (code "87") (name "unconnected-(J2-RESERVED-Pad32)") (class "Default")
      (node (ref "J2") (pin "32") (pinfunction "RESERVED_32") (pintype "passive"))
    )
    (net (code "88") (name "unconnected-(J2-SWCLK{slash}NC-Pad20)") (class "Default")
      (node (ref "J2") (pin "20") (pinfunction "SWCLK/NC_20") (pintype "passive"))
    )
    (net (code "89") (name "unconnected-(J2-SWDIO{slash}NC-Pad19)") (class "Default")
      (node (ref "J2") (pin "19") (pinfunction "SWDIO/NC_19") (pintype "passive"))
    )
    (net (code "90") (name "unconnected-(U1A-RF_N-Pad2)") (class "Default")
      (node (ref "U1") (pin "2") (pinfunction "RF_N_2") (pintype "passive"))
    )
    (net (code "91") (name "unconnected-(U1A-RF_P-Pad1)") (class "Default")
      (node (ref "U1") (pin "1") (pinfunction "RF_P_1") (pintype "passive"))
    )
    (net (code "92") (name "unconnected-(U1A-RX_TX-Pad3)") (class "Default")
      (node (ref "U1") (pin "3") (pinfunction "RX_TX_3") (pintype "passive"))
    )
    (net (code "93") (name "unconnected-(U3-RXTX{slash}RFMOD-Pad20)") (class "Default")
      (node (ref "U3") (pin "20") (pinfunction "RXTX/RFMOD_20") (pintype "passive"))
    )
  )
)
